# Adafruit_Bicolor_8x8_HT16K33_STEMMA.net
KiCad netlist of a schematic drawn in EAGLE
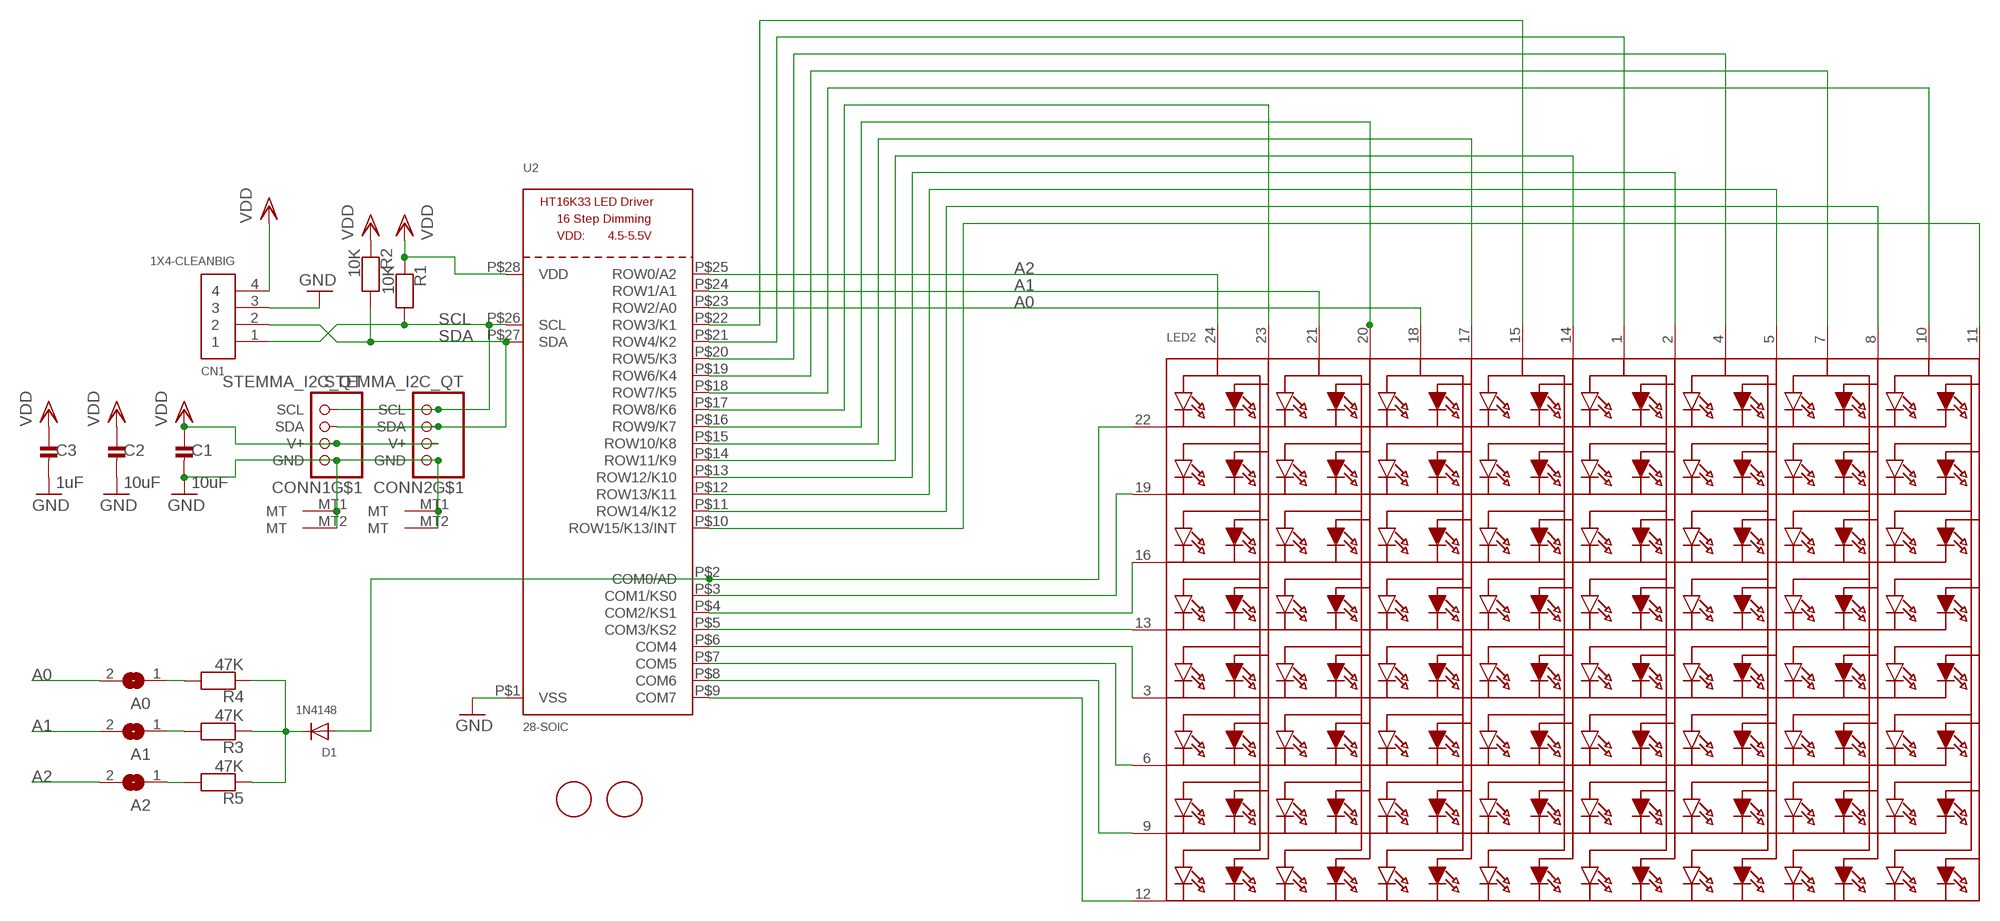
[diagram p0: schematic, sheet 1]

(export (version "E")
  (design (tool "Eeschema 10.0.6"))
  (components
    (comp (ref "A0")
      (value "SOLDERJUMPERREFLOW_NOPASTE")
      (footprint "eagle-import:SOLDERJUMPER_REFLOW_NOPASTE")
      (libsource (lib "eagle-import") (part "SOLDERJUMPERREFLOW_NOPASTE"))
    )
    (comp (ref "A1")
      (value "SOLDERJUMPERREFLOW_NOPASTE")
      (footprint "eagle-import:SOLDERJUMPER_REFLOW_NOPASTE")
      (libsource (lib "eagle-import") (part "SOLDERJUMPERREFLOW_NOPASTE"))
    )
    (comp (ref "A2")
      (value "SOLDERJUMPERREFLOW_NOPASTE")
      (footprint "eagle-import:SOLDERJUMPER_REFLOW_NOPASTE")
      (libsource (lib "eagle-import") (part "SOLDERJUMPERREFLOW_NOPASTE"))
    )
    (comp (ref "C1")
      (value "10uF")
      (footprint "eagle-import:0805-NO")
      (libsource (lib "eagle-import") (part "CAP_CERAMIC0805-NOOUTLINE"))
    )
    (comp (ref "C2")
      (value "10uF")
      (footprint "eagle-import:0805-NO")
      (libsource (lib "eagle-import") (part "CAP_CERAMIC0805-NOOUTLINE"))
    )
    (comp (ref "C3")
      (value "1uF")
      (footprint "eagle-import:0603-NO")
      (libsource (lib "eagle-import") (part "CAP_CERAMIC0603_NO"))
    )
    (comp (ref "CN1")
      (value "1X4-CLEANBIG")
      (footprint "eagle-import:1X04-CLEANBIG")
      (libsource (lib "eagle-import") (part "1X4-CLEANBIG"))
    )
    (comp (ref "CONN1")
      (value "STEMMA_I2C_QT")
      (footprint "eagle-import:JST_SH4")
      (libsource (lib "eagle-import") (part "STEMMA_I2C_QT"))
    )
    (comp (ref "CONN2")
      (value "STEMMA_I2C_QT")
      (footprint "eagle-import:JST_SH4")
      (libsource (lib "eagle-import") (part "STEMMA_I2C_QT"))
    )
    (comp (ref "D1")
      (value "1N4148")
      (footprint "eagle-import:SOD-323")
      (libsource (lib "eagle-import") (part "DIODESOD-323"))
    )
    (comp (ref "LED2")
      (value "DISP_SEGMENT_8X8_BICOLOR_ROWCATHODEMI2A883XX")
      (footprint "eagle-import:SEGMENT_BICOL_BL-M12A883XX")
      (libsource (lib "eagle-import") (part "DISP_SEGMENT_8X8_BICOLOR_ROWCATHODEMI2A883XX"))
    )
    (comp (ref "R1")
      (value "10K")
      (footprint "eagle-import:0603-NO")
      (libsource (lib "eagle-import") (part "RESISTOR_0603_NOOUT"))
    )
    (comp (ref "R2")
      (value "10K")
      (footprint "eagle-import:0603-NO")
      (libsource (lib "eagle-import") (part "RESISTOR_0603_NOOUT"))
    )
    (comp (ref "R3")
      (value "47K")
      (footprint "eagle-import:0603-NO")
      (libsource (lib "eagle-import") (part "RESISTOR_0603_NOOUT"))
    )
    (comp (ref "R4")
      (value "47K")
      (footprint "eagle-import:0603-NO")
      (libsource (lib "eagle-import") (part "RESISTOR_0603_NOOUT"))
    )
    (comp (ref "R5")
      (value "47K")
      (footprint "eagle-import:0603-NO")
      (libsource (lib "eagle-import") (part "RESISTOR_0603_NOOUT"))
    )
    (comp (ref "U$1")
      (value "FIDUCIAL")
      (footprint "eagle-import:FIDUCIAL_1MM")
      (libsource (lib "eagle-import") (part "FIDUCIAL"))
    )
    (comp (ref "U$2")
      (value "FIDUCIAL")
      (footprint "eagle-import:FIDUCIAL_1MM")
      (libsource (lib "eagle-import") (part "FIDUCIAL"))
    )
    (comp (ref "U2")
      (value "28-SOIC")
      (footprint "eagle-import:SOP28_300MIL")
      (libsource (lib "eagle-import") (part "HT16K33_SOP28"))
    )
  )
  (nets
    (net (code "1") (name "/A0") (class "Default")
      (node (ref "A0") (pin "2") (pinfunction "2_2") (pintype "passive"))
      (node (ref "LED2") (pin "18") (pinfunction "A5_18") (pintype "bidirectional"))
      (node (ref "U2") (pin "P$23") (pinfunction "ROW2/A0_P$23") (pintype "bidirectional"))
    )
    (net (code "2") (name "/A1") (class "Default")
      (node (ref "A1") (pin "2") (pinfunction "2_2") (pintype "passive"))
      (node (ref "LED2") (pin "21") (pinfunction "A3_21") (pintype "bidirectional"))
      (node (ref "U2") (pin "P$24") (pinfunction "ROW1/A1_P$24") (pintype "bidirectional"))
    )
    (net (code "3") (name "/A2") (class "Default")
      (node (ref "A2") (pin "2") (pinfunction "2_2") (pintype "passive"))
      (node (ref "LED2") (pin "24") (pinfunction "A1_24") (pintype "bidirectional"))
      (node (ref "U2") (pin "P$25") (pinfunction "ROW0/A2_P$25") (pintype "bidirectional"))
    )
    (net (code "4") (name "/SCL") (class "Default")
      (node (ref "CN1") (pin "1") (pinfunction "1_1") (pintype "bidirectional"))
      (node (ref "CONN1") (pin "4") (pinfunction "SCL_4") (pintype "passive"))
      (node (ref "CONN2") (pin "4") (pinfunction "SCL_4") (pintype "passive"))
      (node (ref "R1") (pin "2") (pinfunction "2_2") (pintype "passive"))
      (node (ref "U2") (pin "P$26") (pinfunction "SCL_P$26") (pintype "bidirectional"))
    )
    (net (code "5") (name "/SDA") (class "Default")
      (node (ref "CN1") (pin "2") (pinfunction "2_2") (pintype "bidirectional"))
      (node (ref "CONN1") (pin "3") (pinfunction "SDA_3") (pintype "passive"))
      (node (ref "CONN2") (pin "3") (pinfunction "SDA_3") (pintype "passive"))
      (node (ref "R2") (pin "2") (pinfunction "2_2") (pintype "passive"))
      (node (ref "U2") (pin "P$27") (pinfunction "SDA_P$27") (pintype "bidirectional"))
    )
    (net (code "6") (name "GND") (class "Default")
      (node (ref "C1") (pin "2") (pinfunction "2_2") (pintype "passive"))
      (node (ref "C2") (pin "2") (pinfunction "2_2") (pintype "passive"))
      (node (ref "C3") (pin "2") (pinfunction "2_2") (pintype "passive"))
      (node (ref "CN1") (pin "3") (pinfunction "3_3") (pintype "bidirectional"))
      (node (ref "CONN1") (pin "1") (pinfunction "GND_1") (pintype "passive"))
      (node (ref "CONN1") (pin "MT1") (pinfunction "MT_MT1") (pintype "bidirectional"))
      (node (ref "CONN1") (pin "MT2") (pinfunction "MT_MT2") (pintype "bidirectional"))
      (node (ref "CONN2") (pin "1") (pinfunction "GND_1") (pintype "passive"))
      (node (ref "CONN2") (pin "MT1") (pinfunction "MT_MT1") (pintype "bidirectional"))
      (node (ref "CONN2") (pin "MT2") (pinfunction "MT_MT2") (pintype "bidirectional"))
      (node (ref "U2") (pin "P$1") (pinfunction "VSS_P$1") (pintype "bidirectional"))
    )
    (net (code "7") (name "Net-(A0-Pad1)") (class "Default")
      (node (ref "A0") (pin "1") (pinfunction "1_1") (pintype "passive"))
      (node (ref "R4") (pin "2") (pinfunction "2_2") (pintype "passive"))
    )
    (net (code "8") (name "Net-(A1-Pad1)") (class "Default")
      (node (ref "A1") (pin "1") (pinfunction "1_1") (pintype "passive"))
      (node (ref "R3") (pin "2") (pinfunction "2_2") (pintype "passive"))
    )
    (net (code "9") (name "Net-(A2-Pad1)") (class "Default")
      (node (ref "A2") (pin "1") (pinfunction "1_1") (pintype "passive"))
      (node (ref "R5") (pin "2") (pinfunction "2_2") (pintype "passive"))
    )
    (net (code "10") (name "Net-(D1-PadC)") (class "Default")
      (node (ref "D1") (pin "C") (pinfunction "C_C") (pintype "passive"))
      (node (ref "R3") (pin "1") (pinfunction "1_1") (pintype "passive"))
      (node (ref "R4") (pin "1") (pinfunction "1_1") (pintype "passive"))
      (node (ref "R5") (pin "1") (pinfunction "1_1") (pintype "passive"))
    )
    (net (code "11") (name "Net-(LED2-A2)") (class "Default")
      (node (ref "LED2") (pin "23") (pinfunction "A2_23") (pintype "bidirectional"))
      (node (ref "U2") (pin "P$17") (pinfunction "ROW8/K6_P$17") (pintype "bidirectional"))
    )
    (net (code "12") (name "Net-(LED2-A4)") (class "Default")
      (node (ref "LED2") (pin "20") (pinfunction "A4_20") (pintype "bidirectional"))
      (node (ref "U2") (pin "P$16") (pinfunction "ROW9/K7_P$16") (pintype "bidirectional"))
    )
    (net (code "13") (name "Net-(LED2-A6)") (class "Default")
      (node (ref "LED2") (pin "17") (pinfunction "A6_17") (pintype "bidirectional"))
      (node (ref "U2") (pin "P$15") (pinfunction "ROW10/K8_P$15") (pintype "bidirectional"))
    )
    (net (code "14") (name "Net-(LED2-A7)") (class "Default")
      (node (ref "LED2") (pin "15") (pinfunction "A7_15") (pintype "bidirectional"))
      (node (ref "U2") (pin "P$22") (pinfunction "ROW3/K1_P$22") (pintype "bidirectional"))
    )
    (net (code "15") (name "Net-(LED2-A8)") (class "Default")
      (node (ref "LED2") (pin "14") (pinfunction "A8_14") (pintype "bidirectional"))
      (node (ref "U2") (pin "P$14") (pinfunction "ROW11/K9_P$14") (pintype "bidirectional"))
    )
    (net (code "16") (name "Net-(LED2-A9)") (class "Default")
      (node (ref "LED2") (pin "1") (pinfunction "A9_1") (pintype "bidirectional"))
      (node (ref "U2") (pin "P$21") (pinfunction "ROW4/K2_P$21") (pintype "bidirectional"))
    )
    (net (code "17") (name "Net-(LED2-A10)") (class "Default")
      (node (ref "LED2") (pin "2") (pinfunction "A10_2") (pintype "bidirectional"))
      (node (ref "U2") (pin "P$13") (pinfunction "ROW12/K10_P$13") (pintype "bidirectional"))
    )
    (net (code "18") (name "Net-(LED2-A11)") (class "Default")
      (node (ref "LED2") (pin "4") (pinfunction "A11_4") (pintype "bidirectional"))
      (node (ref "U2") (pin "P$20") (pinfunction "ROW5/K3_P$20") (pintype "bidirectional"))
    )
    (net (code "19") (name "Net-(LED2-A12)") (class "Default")
      (node (ref "LED2") (pin "5") (pinfunction "A12_5") (pintype "bidirectional"))
      (node (ref "U2") (pin "P$12") (pinfunction "ROW13/K11_P$12") (pintype "bidirectional"))
    )
    (net (code "20") (name "Net-(LED2-A13)") (class "Default")
      (node (ref "LED2") (pin "7") (pinfunction "A13_7") (pintype "bidirectional"))
      (node (ref "U2") (pin "P$19") (pinfunction "ROW6/K4_P$19") (pintype "bidirectional"))
    )
    (net (code "21") (name "Net-(LED2-A14)") (class "Default")
      (node (ref "LED2") (pin "8") (pinfunction "A14_8") (pintype "bidirectional"))
      (node (ref "U2") (pin "P$11") (pinfunction "ROW14/K12_P$11") (pintype "bidirectional"))
    )
    (net (code "22") (name "Net-(LED2-A15)") (class "Default")
      (node (ref "LED2") (pin "10") (pinfunction "A15_10") (pintype "bidirectional"))
      (node (ref "U2") (pin "P$18") (pinfunction "ROW7/K5_P$18") (pintype "bidirectional"))
    )
    (net (code "23") (name "Net-(LED2-A16)") (class "Default")
      (node (ref "LED2") (pin "11") (pinfunction "A16_11") (pintype "bidirectional"))
      (node (ref "U2") (pin "P$10") (pinfunction "ROW15/K13/INT_P$10") (pintype "bidirectional"))
    )
    (net (code "24") (name "Net-(LED2-K1)") (class "Default")
      (node (ref "D1") (pin "A") (pinfunction "A_A") (pintype "passive"))
      (node (ref "LED2") (pin "22") (pinfunction "K1_22") (pintype "bidirectional"))
      (node (ref "U2") (pin "P$2") (pinfunction "COM0/AD_P$2") (pintype "bidirectional"))
    )
    (net (code "25") (name "Net-(LED2-K2)") (class "Default")
      (node (ref "LED2") (pin "19") (pinfunction "K2_19") (pintype "bidirectional"))
      (node (ref "U2") (pin "P$3") (pinfunction "COM1/KS0_P$3") (pintype "bidirectional"))
    )
    (net (code "26") (name "Net-(LED2-K3)") (class "Default")
      (node (ref "LED2") (pin "16") (pinfunction "K3_16") (pintype "bidirectional"))
      (node (ref "U2") (pin "P$4") (pinfunction "COM2/KS1_P$4") (pintype "bidirectional"))
    )
    (net (code "27") (name "Net-(LED2-K4)") (class "Default")
      (node (ref "LED2") (pin "13") (pinfunction "K4_13") (pintype "bidirectional"))
      (node (ref "U2") (pin "P$5") (pinfunction "COM3/KS2_P$5") (pintype "bidirectional"))
    )
    (net (code "28") (name "Net-(LED2-K5)") (class "Default")
      (node (ref "LED2") (pin "3") (pinfunction "K5_3") (pintype "bidirectional"))
      (node (ref "U2") (pin "P$6") (pinfunction "COM4_P$6") (pintype "bidirectional"))
    )
    (net (code "29") (name "Net-(LED2-K6)") (class "Default")
      (node (ref "LED2") (pin "6") (pinfunction "K6_6") (pintype "bidirectional"))
      (node (ref "U2") (pin "P$7") (pinfunction "COM5_P$7") (pintype "bidirectional"))
    )
    (net (code "30") (name "Net-(LED2-K7)") (class "Default")
      (node (ref "LED2") (pin "9") (pinfunction "K7_9") (pintype "bidirectional"))
      (node (ref "U2") (pin "P$8") (pinfunction "COM6_P$8") (pintype "bidirectional"))
    )
    (net (code "31") (name "Net-(LED2-K8)") (class "Default")
      (node (ref "LED2") (pin "12") (pinfunction "K8_12") (pintype "bidirectional"))
      (node (ref "U2") (pin "P$9") (pinfunction "COM7_P$9") (pintype "bidirectional"))
    )
    (net (code "32") (name "VDD") (class "Default")
      (node (ref "C1") (pin "1") (pinfunction "1_1") (pintype "passive"))
      (node (ref "C2") (pin "1") (pinfunction "1_1") (pintype "passive"))
      (node (ref "C3") (pin "1") (pinfunction "1_1") (pintype "passive"))
      (node (ref "CN1") (pin "4") (pinfunction "4_4") (pintype "bidirectional"))
      (node (ref "CONN1") (pin "2") (pinfunction "V+_2") (pintype "passive"))
      (node (ref "CONN2") (pin "2") (pinfunction "V+_2") (pintype "passive"))
      (node (ref "R1") (pin "1") (pinfunction "1_1") (pintype "passive"))
      (node (ref "R2") (pin "1") (pinfunction "1_1") (pintype "passive"))
      (node (ref "U2") (pin "P$28") (pinfunction "VDD_P$28") (pintype "bidirectional"))
    )
  )
)
